# OSSI-1_EPS_2.net
KiCad netlist of a schematic drawn in Altium Designer
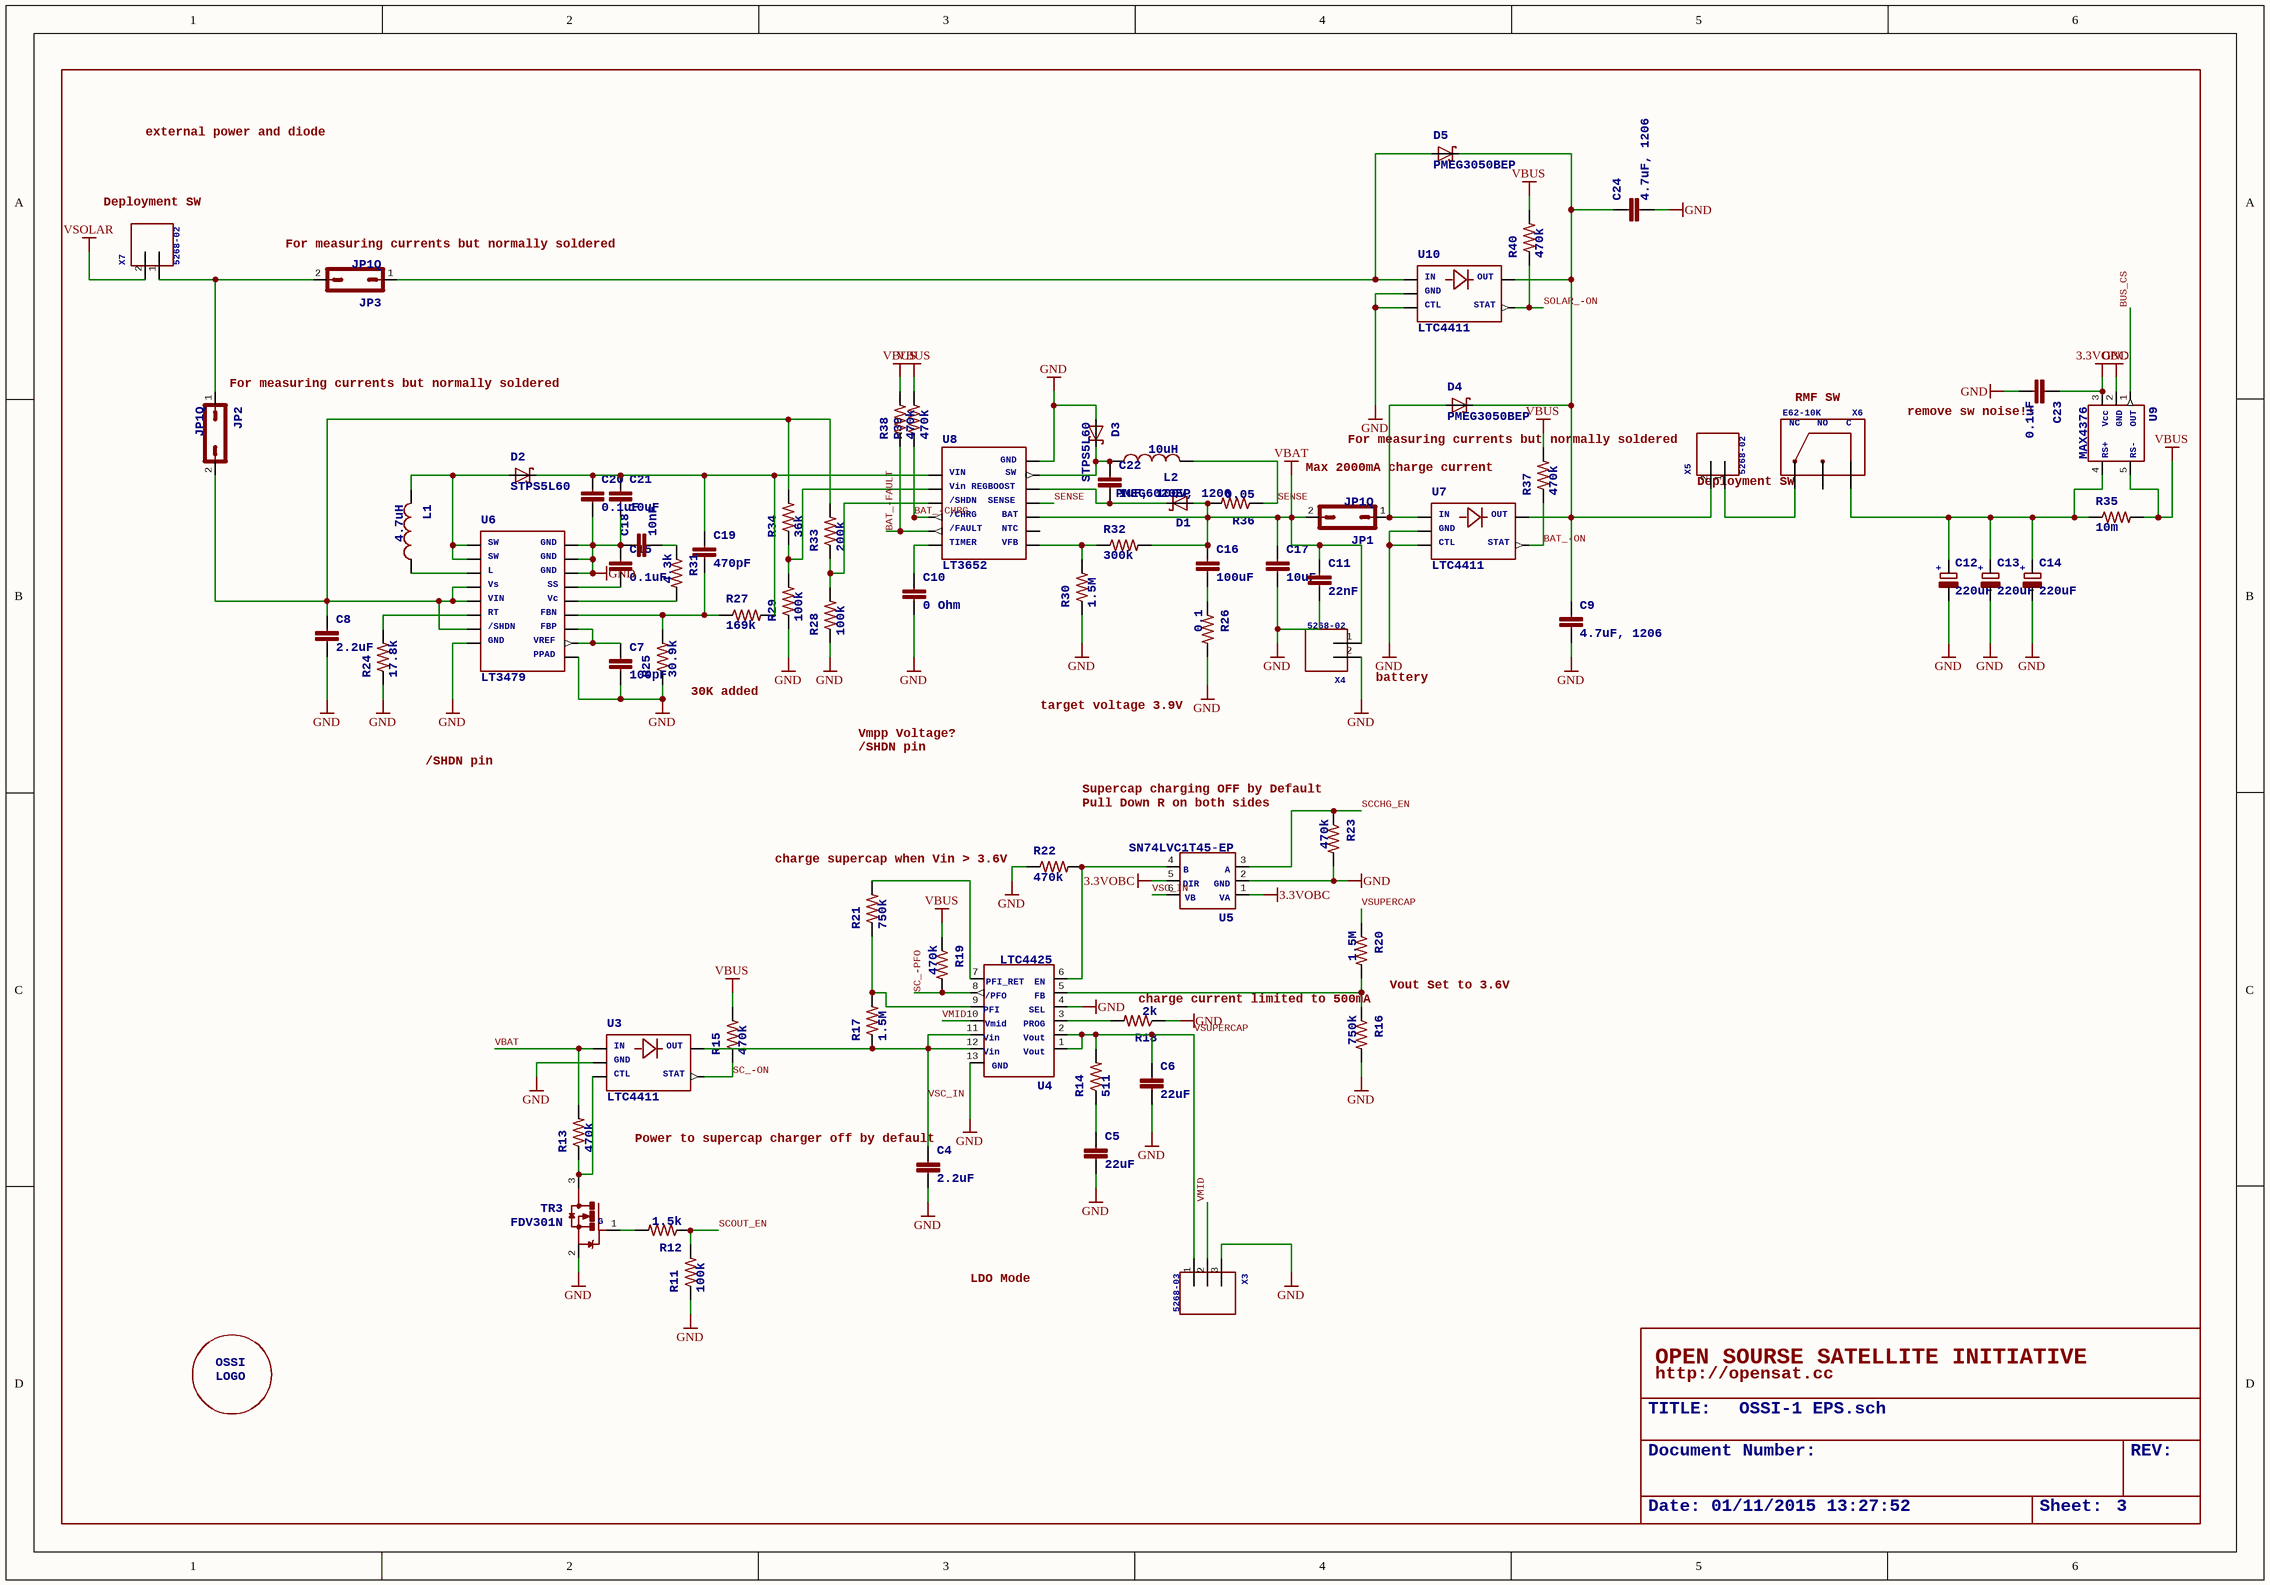
[diagram p0: OSSI-1 EPS_2.SchDoc]

(export (version "E")
  (design (tool "Eeschema 10.0.6"))
  (components
    (comp (ref "C4")
      (value "2.2uF")
      (footprint "C1206-GCM31")
      (fields (field (name ">NAME") "C4") (field (name ">VALUE") "2.2uF"))
      (libsource (lib "OSSI") (part "C1206(3216)-GCM31"))
    )
    (comp (ref "C5")
      (value "22uF")
      (footprint "C1210-GCM32")
      (fields (field (name ">NAME") "C5") (field (name ">VALUE") "22uF"))
      (libsource (lib "OSSI") (part "C1210(3225)-GCM32"))
    )
    (comp (ref "C6")
      (value "22uF")
      (footprint "C1210-GCM32")
      (fields (field (name ">NAME") "C6") (field (name ">VALUE") "22uF"))
      (libsource (lib "OSSI") (part "C1210(3225)-GCM32"))
    )
    (comp (ref "C7")
      (value "100pF")
      (footprint "C0603(1608)")
      (fields (field (name ">NAME") "C7") (field (name ">VALUE") "100pF"))
      (libsource (lib "OSSI") (part "C0603(1608)"))
    )
    (comp (ref "C8")
      (value "2.2uF")
      (footprint "C1206-GCM31")
      (fields (field (name ">NAME") "C8") (field (name ">VALUE") "2.2uF"))
      (libsource (lib "OSSI") (part "C1206(3216)-GCM31"))
    )
    (comp (ref "C9")
      (value "4.7uF, 1206")
      (footprint "C1206-GCM31")
      (fields (field (name ">NAME") "C9") (field (name ">VALUE") "4.7uF, 1206"))
      (libsource (lib "OSSI") (part "C1206(3216)-GCM31"))
    )
    (comp (ref "C10")
      (value "0 Ohm")
      (footprint "C0603(1608)")
      (fields (field (name ">NAME") "C10") (field (name ">VALUE") "0 Ohm"))
      (libsource (lib "OSSI") (part "C0603(1608)"))
    )
    (comp (ref "C11")
      (value "22nF")
      (footprint "C0603(1608)")
      (fields (field (name ">NAME") "C11") (field (name ">VALUE") "22nF"))
      (libsource (lib "OSSI") (part "C0603(1608)"))
    )
    (comp (ref "C12")
      (value "220uF")
      (footprint "C2917(7343)-Y")
      (fields (field (name ">NAME") "C12") (field (name "+") "+") (field (name ">VALUE") "220uF"))
      (libsource (lib "OSSI") (part "C-TANTAL-Y"))
    )
    (comp (ref "C13")
      (value "220uF")
      (footprint "C2917(7343)-Y")
      (fields (field (name ">NAME") "C13") (field (name "+") "+") (field (name ">VALUE") "220uF"))
      (libsource (lib "OSSI") (part "C-TANTAL-Y"))
    )
    (comp (ref "C14")
      (value "220uF")
      (footprint "C2917(7343)-Y")
      (fields (field (name ">NAME") "C14") (field (name "+") "+") (field (name ">VALUE") "220uF"))
      (libsource (lib "OSSI") (part "C-TANTAL-Y"))
    )
    (comp (ref "C15")
      (value "0.1uF")
      (footprint "C0603(1608)")
      (fields (field (name ">NAME") "C15") (field (name ">VALUE") "0.1uF"))
      (libsource (lib "OSSI") (part "C0603(1608)"))
    )
    (comp (ref "C16")
      (value "100uF")
      (footprint "C1210-TMK325")
      (fields (field (name ">NAME") "C16") (field (name ">VALUE") "100uF"))
      (libsource (lib "OSSI") (part "C1210(3225)-TMK325"))
    )
    (comp (ref "C17")
      (value "10uF")
      (footprint "C1210-GCM32")
      (fields (field (name ">NAME") "C17") (field (name ">VALUE") "10uF"))
      (libsource (lib "OSSI") (part "C1210(3225)-GCM32"))
    )
    (comp (ref "C18")
      (value "10nF")
      (footprint "C0603(1608)")
      (fields (field (name ">NAME") "C18") (field (name ">VALUE") "10nF"))
      (libsource (lib "") (part "C0603(1608)_2"))
    )
    (comp (ref "C19")
      (value "470pF")
      (footprint "C0603(1608)")
      (fields (field (name ">NAME") "C19") (field (name ">VALUE") "470pF"))
      (libsource (lib "OSSI") (part "C0603(1608)"))
    )
    (comp (ref "C20")
      (value "0.1uF")
      (footprint "C0603(1608)")
      (fields (field (name ">NAME") "C20") (field (name ">VALUE") "0.1uF"))
      (libsource (lib "OSSI") (part "C0603(1608)"))
    )
    (comp (ref "C21")
      (value "10uF")
      (footprint "C1210-GCM32")
      (fields (field (name ">NAME") "C21") (field (name ">VALUE") "10uF"))
      (libsource (lib "OSSI") (part "C1210(3225)-GCM32"))
    )
    (comp (ref "C22")
      (value "1uF, 100V, 1206")
      (footprint "C0805(2012)")
      (fields (field (name ">NAME") "C22") (field (name ">VALUE") "1uF, 100V, 1206"))
      (libsource (lib "OSSI") (part "C0805(2012)"))
    )
    (comp (ref "C23")
      (value "0.1uF")
      (footprint "C0603(1608)")
      (fields (field (name ">NAME") "C23") (field (name ">VALUE") "0.1uF"))
      (libsource (lib "") (part "C0603(1608)_1"))
    )
    (comp (ref "C24")
      (value "4.7uF, 1206")
      (footprint "C1206-GCM31")
      (fields (field (name ">NAME") "C24") (field (name ">VALUE") "4.7uF, 1206"))
      (libsource (lib "") (part "C1206(3216)-GCM31_1"))
    )
    (comp (ref "D1")
      (value "PMEG6020EP")
      (footprint "PMEG6020EP")
      (fields (field (name ">NAME") "D1") (field (name ">VALUE") "PMEG6020EP"))
      (libsource (lib "OSSI") (part "PMEG6020EP"))
    )
    (comp (ref "D2")
      (value "STPS5L60")
      (footprint "STPS5L60")
      (description "<b>STPS5L60</b>\nIf: 5A / Vrrm: 60V / Vf: 0.47V @ 5A")
      (fields (field (name ">NAME") "D2") (field (name ">VALUE") "STPS5L60"))
      (libsource (lib "OSSI") (part "STPS5L60"))
    )
    (comp (ref "D3")
      (value "STPS5L60")
      (footprint "STPS5L60")
      (description "<b>STPS5L60</b>\nIf: 5A / Vrrm: 60V / Vf: 0.47V @ 5A")
      (fields (field (name ">NAME") "D3") (field (name ">VALUE") "STPS5L60"))
      (libsource (lib "OSSI") (part "STPS5L60"))
    )
    (comp (ref "D4")
      (value "PMEG3050BEP")
      (footprint "PMEG6020EP")
      (fields (field (name ">NAME") "D4") (field (name ">VALUE") "PMEG3050BEP"))
      (libsource (lib "OSSI") (part "PMEG6020EP"))
    )
    (comp (ref "D5")
      (value "PMEG3050BEP")
      (footprint "PMEG6020EP")
      (fields (field (name ">NAME") "D5") (field (name ">VALUE") "PMEG3050BEP"))
      (libsource (lib "OSSI") (part "PMEG6020EP"))
    )
    (comp (ref "JP1")
      (value "JP1Q")
      (footprint "JP1")
      (description "<b>JUMPER</b>")
      (fields (field (name ">NAME") "JP1") (field (name ">VALUE") "JP1Q"))
      (libsource (lib "OSSI") (part "JP1Q"))
    )
    (comp (ref "JP2")
      (value "JP1Q")
      (footprint "JP1")
      (description "<b>JUMPER</b>")
      (fields (field (name ">NAME") "JP2") (field (name ">VALUE") "JP1Q"))
      (libsource (lib "OSSI") (part "JP1Q"))
    )
    (comp (ref "JP3")
      (value "JP1Q")
      (footprint "JP1")
      (description "<b>JUMPER</b>")
      (fields (field (name ">NAME") "JP3") (field (name ">VALUE") "JP1Q"))
      (libsource (lib "OSSI") (part "JP1Q"))
    )
    (comp (ref "L1")
      (value "4.7uH")
      (footprint "RLF7030")
      (fields (field (name ">NAME") "L1") (field (name ">VALUE") "4.7uH"))
      (libsource (lib "OSSI") (part "LRLF7030"))
    )
    (comp (ref "L2")
      (value "10uH")
      (footprint "RLF12545")
      (fields (field (name ">NAME") "L2") (field (name ">VALUE") "10uH"))
      (libsource (lib "OSSI") (part "LRLF12545"))
    )
    (comp (ref "R11")
      (value "100k")
      (footprint "R0603(1608)")
      (fields (field (name ">NAME") "R11") (field (name ">VALUE") "100k"))
      (libsource (lib "OSSI") (part "R0603(1608)"))
    )
    (comp (ref "R12")
      (value "1.5k")
      (footprint "R0603(1608)")
      (fields (field (name ">NAME") "R12") (field (name ">VALUE") "1.5k"))
      (libsource (lib "OSSI") (part "R0603(1608)"))
    )
    (comp (ref "R13")
      (value "470k")
      (footprint "R0603(1608)")
      (fields (field (name ">NAME") "R13") (field (name ">VALUE") "470k"))
      (libsource (lib "OSSI") (part "R0603(1608)"))
    )
    (comp (ref "R14")
      (value "511")
      (footprint "WSL1206")
      (fields (field (name ">NAME") "R14") (field (name ">VALUE") "511"))
      (libsource (lib "OSSI") (part "RWSL1206"))
    )
    (comp (ref "R15")
      (value "470k")
      (footprint "R0603(1608)")
      (fields (field (name ">NAME") "R15") (field (name ">VALUE") "470k"))
      (libsource (lib "OSSI") (part "R0603(1608)"))
    )
    (comp (ref "R16")
      (value "750k")
      (footprint "R0603(1608)")
      (fields (field (name ">NAME") "R16") (field (name ">VALUE") "750k"))
      (libsource (lib "OSSI") (part "R0603(1608)"))
    )
    (comp (ref "R17")
      (value "1.5M")
      (footprint "R0603(1608)")
      (fields (field (name ">NAME") "R17") (field (name ">VALUE") "1.5M"))
      (libsource (lib "OSSI") (part "R0603(1608)"))
    )
    (comp (ref "R18")
      (value "2k")
      (footprint "R0603(1608)")
      (fields (field (name ">NAME") "R18") (field (name ">VALUE") "2k"))
      (libsource (lib "OSSI") (part "R0603(1608)"))
    )
    (comp (ref "R19")
      (value "470k")
      (footprint "R0603(1608)")
      (fields (field (name ">NAME") "R19") (field (name ">VALUE") "470k"))
      (libsource (lib "OSSI") (part "R0603(1608)"))
    )
    (comp (ref "R20")
      (value "1.5M")
      (footprint "R0603(1608)")
      (fields (field (name ">NAME") "R20") (field (name ">VALUE") "1.5M"))
      (libsource (lib "OSSI") (part "R0603(1608)"))
    )
    (comp (ref "R21")
      (value "750k")
      (footprint "R0603(1608)")
      (fields (field (name ">NAME") "R21") (field (name ">VALUE") "750k"))
      (libsource (lib "OSSI") (part "R0603(1608)"))
    )
    (comp (ref "R22")
      (value "470k")
      (footprint "R0603(1608)")
      (fields (field (name ">NAME") "R22") (field (name ">VALUE") "470k"))
      (libsource (lib "OSSI") (part "R0603(1608)"))
    )
    (comp (ref "R23")
      (value "470k")
      (footprint "R0603(1608)")
      (fields (field (name ">NAME") "R23") (field (name ">VALUE") "470k"))
      (libsource (lib "OSSI") (part "R0603(1608)"))
    )
    (comp (ref "R24")
      (value "17.8k")
      (footprint "R0603(1608)")
      (fields (field (name ">NAME") "R24") (field (name ">VALUE") "17.8k"))
      (libsource (lib "OSSI") (part "R0603(1608)"))
    )
    (comp (ref "R25")
      (value "30.9k")
      (footprint "R0603(1608)")
      (fields (field (name ">NAME") "R25") (field (name ">VALUE") "30.9k"))
      (libsource (lib "OSSI") (part "R0603(1608)"))
    )
    (comp (ref "R26")
      (value "0.1")
      (footprint "WSL1206")
      (fields (field (name ">NAME") "R26") (field (name ">VALUE") "0.1"))
      (libsource (lib "OSSI") (part "RWSL1206"))
    )
    (comp (ref "R27")
      (value "169k")
      (footprint "R0603(1608)")
      (fields (field (name ">NAME") "R27") (field (name ">VALUE") "169k"))
      (libsource (lib "OSSI") (part "R0603(1608)"))
    )
    (comp (ref "R28")
      (value "100k")
      (footprint "R0603(1608)")
      (fields (field (name ">NAME") "R28") (field (name ">VALUE") "100k"))
      (libsource (lib "OSSI") (part "R0603(1608)"))
    )
    (comp (ref "R29")
      (value "100k")
      (footprint "R0603(1608)")
      (fields (field (name ">NAME") "R29") (field (name ">VALUE") "100k"))
      (libsource (lib "OSSI") (part "R0603(1608)"))
    )
    (comp (ref "R30")
      (value "1.5M")
      (footprint "R0603(1608)")
      (fields (field (name ">NAME") "R30") (field (name ">VALUE") "1.5M"))
      (libsource (lib "OSSI") (part "R0603(1608)"))
    )
    (comp (ref "R31")
      (value "4.3k")
      (footprint "R0603(1608)")
      (fields (field (name ">NAME") "R31") (field (name ">VALUE") "4.3k"))
      (libsource (lib "OSSI") (part "R0603(1608)"))
    )
    (comp (ref "R32")
      (value "300k")
      (footprint "R0603(1608)")
      (fields (field (name ">NAME") "R32") (field (name ">VALUE") "300k"))
      (libsource (lib "OSSI") (part "R0603(1608)"))
    )
    (comp (ref "R33")
      (value "200k")
      (footprint "R0603(1608)")
      (fields (field (name ">NAME") "R33") (field (name ">VALUE") "200k"))
      (libsource (lib "OSSI") (part "R0603(1608)"))
    )
    (comp (ref "R34")
      (value "36k")
      (footprint "R0603(1608)")
      (fields (field (name ">NAME") "R34") (field (name ">VALUE") "36k"))
      (libsource (lib "OSSI") (part "R0603(1608)"))
    )
    (comp (ref "R35")
      (value "10m")
      (footprint "WSL1206")
      (fields (field (name ">NAME") "R35") (field (name ">VALUE") "10m"))
      (libsource (lib "OSSI") (part "RWSL1206"))
    )
    (comp (ref "R36")
      (value "0.05")
      (footprint "WSL1206")
      (fields (field (name ">NAME") "R36") (field (name ">VALUE") "0.05"))
      (libsource (lib "OSSI") (part "RWSL1206"))
    )
    (comp (ref "R37")
      (value "470k")
      (footprint "R0603(1608)")
      (fields (field (name ">NAME") "R37") (field (name ">VALUE") "470k"))
      (libsource (lib "OSSI") (part "R0603(1608)"))
    )
    (comp (ref "R38")
      (value "470k")
      (footprint "R0603(1608)")
      (fields (field (name ">NAME") "R38") (field (name ">VALUE") "470k"))
      (libsource (lib "OSSI") (part "R0603(1608)"))
    )
    (comp (ref "R39")
      (value "470k")
      (footprint "R0603(1608)")
      (fields (field (name ">NAME") "R39") (field (name ">VALUE") "470k"))
      (libsource (lib "OSSI") (part "R0603(1608)"))
    )
    (comp (ref "R40")
      (value "470k")
      (footprint "R0603(1608)")
      (fields (field (name ">NAME") "R40") (field (name ">VALUE") "470k"))
      (libsource (lib "OSSI") (part "R0603(1608)"))
    )
    (comp (ref "TR3")
      (value "FDV301N")
      (footprint "SOT23")
      (description "FDV301N Digital N channel - FET / Rdson = 5 Ohm / Vgs = 0.7~1.06V / Ids = 220mA")
      (fields (field (name "G") "G") (field (name ">NAME") "TR3") (field (name ">VALUE") "FDV301N"))
      (libsource (lib "OSSI") (part "FDV301N"))
    )
    (comp (ref "U$1")
      (value "OSSILOGORECT")
      (footprint "OSSILOGORECT1005")
      (fields (field (name "OSSI") "OSSI") (field (name "LOGO") "LOGO"))
      (libsource (lib "OSSI") (part "OSSILOGORECT"))
    )
    (comp (ref "U3")
      (value "LTC4411")
      (footprint "TSOT23-5")
      (fields
        (field (name "IN") "IN")
        (field (name "GND") "GND")
        (field (name "CTL") "CTL")
        (field (name "OUT") "OUT")
        (field (name "STAT") "STAT")
        (field (name ">NAME") "U3")
        (field (name ">VALUE") "LTC4411")
      )
      (libsource (lib "OSSI") (part "LTC4411"))
    )
    (comp (ref "U4")
      (value "LTC4425")
      (footprint "MSE")
      (description "LTC4425 Linear SuperCap Charger With Current-Limited Ideal Diode and V/I Monitor")
      (fields
        (field (name ">NAME") "U4")
        (field (name ">VALUE") "LTC4425")
        (field (name "VOUT") "Vout")
        (field (name "VOUT_1") "Vout")
        (field (name "PROG") "PROG")
        (field (name "SEL") "SEL")
        (field (name "FB") "FB")
        (field (name "EN") "EN")
        (field (name "PFI_RET") "PFI_RET")
        (field (name "/PFO") "/PFO")
        (field (name "VMID") "Vmid")
        (field (name "VIN") "Vin")
        (field (name "VIN_1") "Vin")
        (field (name "PFI") "PFI")
        (field (name "GND") "GND")
      )
      (libsource (lib "OSSI") (part "LTC4425"))
    )
    (comp (ref "U5")
      (value "SN74LVC1T45-EP")
      (footprint "SOT-6DCK")
      (fields
        (field (name ">NAME") "U5")
        (field (name ">VALUE") "SN74LVC1T45-EP")
        (field (name "VA") "VA")
        (field (name "GND") "GND")
        (field (name "A") "A")
        (field (name "B") "B")
        (field (name "DIR") "DIR")
        (field (name "VB") "VB")
      )
      (libsource (lib "OSSI") (part "SN74LVC1T45-EP"))
    )
    (comp (ref "U6")
      (value "LT3479")
      (footprint "TSSOP16-FE")
      (fields
        (field (name "SW") "SW")
        (field (name "SW_1") "SW")
        (field (name "L") "L")
        (field (name "VS") "Vs")
        (field (name "VIN") "VIN")
        (field (name "RT") "RT")
        (field (name "/SHDN") "/SHDN")
        (field (name "GND") "GND")
        (field (name "GND_1") "GND")
        (field (name "GND_2") "GND")
        (field (name "GND_3") "GND")
        (field (name "SS") "SS")
        (field (name "VC") "Vc")
        (field (name "FBN") "FBN")
        (field (name "FBP") "FBP")
        (field (name "VREF") "VREF")
        (field (name ">NAME") "U6")
        (field (name ">VALUE") "LT3479")
        (field (name "PPAD") "PPAD")
      )
      (libsource (lib "OSSI") (part "LT3479"))
    )
    (comp (ref "U7")
      (value "LTC4411")
      (footprint "TSOT23-5")
      (fields
        (field (name "IN") "IN")
        (field (name "GND") "GND")
        (field (name "CTL") "CTL")
        (field (name "OUT") "OUT")
        (field (name "STAT") "STAT")
        (field (name ">NAME") "U7")
        (field (name ">VALUE") "LTC4411")
      )
      (libsource (lib "OSSI") (part "LTC4411"))
    )
    (comp (ref "U8")
      (value "LT3652")
      (footprint "MSE")
      (fields
        (field (name "VIN") "VIN")
        (field (name "VIN REG") "Vin REG")
        (field (name "/SHDN") "/SHDN")
        (field (name "/CHRG") "/CHRG")
        (field (name "/FAULT") "/FAULT")
        (field (name "TIMER") "TIMER")
        (field (name "VFB") "VFB")
        (field (name "NTC") "NTC")
        (field (name "BAT") "BAT")
        (field (name "SENSE") "SENSE")
        (field (name "BOOST") "BOOST")
        (field (name "SW") "SW")
        (field (name ">NAME") "U8")
        (field (name ">VALUE") "LT3652")
        (field (name "GND") "GND")
      )
      (libsource (lib "OSSI") (part "LT3652"))
    )
    (comp (ref "U9")
      (value "MAX4376")
      (footprint "SOT23-5DBV")
      (fields
        (field (name ">NAME") "U9")
        (field (name ">VALUE") "MAX4376")
        (field (name "OUT") "OUT")
        (field (name "GND") "GND")
        (field (name "VCC") "Vcc")
        (field (name "RS+") "RS+")
        (field (name "RS-") "RS-")
      )
      (libsource (lib "OSSI") (part "MAX4376"))
    )
    (comp (ref "U10")
      (value "LTC4411")
      (footprint "TSOT23-5")
      (fields
        (field (name "IN") "IN")
        (field (name "GND") "GND")
        (field (name "CTL") "CTL")
        (field (name "OUT") "OUT")
        (field (name "STAT") "STAT")
        (field (name ">NAME") "U10")
        (field (name ">VALUE") "LTC4411")
      )
      (libsource (lib "OSSI") (part "LTC4411"))
    )
    (comp (ref "X3")
      (value "5268-03")
      (footprint "5268-03")
      (fields (field (name ">NAME") "X3") (field (name ">VALUE") "5268-03"))
      (libsource (lib "OSSI") (part "5268-03"))
    )
    (comp (ref "X4")
      (value "5268-02")
      (footprint "5628-02")
      (fields (field (name ">NAME") "X4") (field (name ">VALUE") "5268-02"))
      (libsource (lib "OSSI") (part "5268-02"))
    )
    (comp (ref "X5")
      (value "5268-02")
      (footprint "5628-02")
      (fields (field (name ">NAME") "X5") (field (name ">VALUE") "5268-02"))
      (libsource (lib "OSSI") (part "5268-02"))
    )
    (comp (ref "X6")
      (value "E62-10K")
      (footprint "E62-10K")
      (description "Cherry E620-10K spdt sw for Remove Before Flight pin")
      (fields
        (field (name ">NAME") "X6")
        (field (name ">VALUE") "E62-10K")
        (field (name "C") "C")
        (field (name "NO") "NO")
        (field (name "NC") "NC")
      )
      (libsource (lib "OSSI") (part "E62-10K"))
    )
    (comp (ref "X7")
      (value "5268-02")
      (footprint "5628-02")
      (fields (field (name ">NAME") "X7") (field (name ">VALUE") "5268-02"))
      (libsource (lib "OSSI") (part "5268-02"))
    )
  )
  (nets
    (net (code "1") (name "/BAT_-CHRG") (class "Default")
      (node (ref "R39") (pin "1") (pinfunction "1_1") (pintype "passive"))
      (node (ref "U8") (pin "4") (pinfunction "P$4_4") (pintype "output"))
    )
    (net (code "2") (name "/BAT_-FAULT") (class "Default")
      (node (ref "R38") (pin "1") (pinfunction "1_1") (pintype "passive"))
      (node (ref "U8") (pin "5") (pinfunction "P$5_5") (pintype "output"))
    )
    (net (code "3") (name "/BAT_-ON") (class "Default")
      (node (ref "R37") (pin "1") (pinfunction "1_1") (pintype "passive"))
      (node (ref "U7") (pin "P$4") (pinfunction "P$4_P$4") (pintype "output"))
    )
    (net (code "4") (name "/BUS_CS") (class "Default")
      (node (ref "U9") (pin "1") (pinfunction "P$1_1") (pintype "output"))
    )
    (net (code "5") (name "/SCCHG_EN") (class "Default")
      (node (ref "R23") (pin "1") (pinfunction "1_1") (pintype "passive"))
      (node (ref "U5") (pin "3") (pinfunction "P$3_3") (pintype "passive"))
    )
    (net (code "6") (name "/SCOUT_EN") (class "Default")
      (node (ref "R11") (pin "2") (pinfunction "2_2") (pintype "passive"))
      (node (ref "R12") (pin "1") (pinfunction "1_1") (pintype "passive"))
    )
    (net (code "7") (name "/SC_-ON") (class "Default")
      (node (ref "R15") (pin "1") (pinfunction "1_1") (pintype "passive"))
      (node (ref "U3") (pin "P$4") (pinfunction "P$4_P$4") (pintype "output"))
    )
    (net (code "8") (name "/SC_-PFO") (class "Default")
      (node (ref "R19") (pin "2") (pinfunction "2_2") (pintype "passive"))
      (node (ref "U4") (pin "8") (pinfunction "P$8_8") (pintype "output"))
    )
    (net (code "9") (name "/SENSE") (class "Default")
      (node (ref "L2") (pin "P$2") (pinfunction "2_P$2") (pintype "passive"))
      (node (ref "R36") (pin "P$1") (pinfunction "1_P$1") (pintype "passive"))
      (node (ref "U8") (pin "10") (pinfunction "P$10_10") (pintype "passive"))
    )
    (net (code "10") (name "/SOLAR_-ON") (class "Default")
      (node (ref "R40") (pin "1") (pinfunction "1_1") (pintype "passive"))
      (node (ref "U10") (pin "P$4") (pinfunction "P$4_P$4") (pintype "output"))
    )
    (net (code "11") (name "/VMID") (class "Default")
      (node (ref "U4") (pin "10") (pinfunction "P$10_10") (pintype "power_in"))
      (node (ref "X3") (pin "2") (pinfunction "2_2") (pintype "passive"))
    )
    (net (code "12") (name "/VSC_IN") (class "Default")
      (node (ref "C4") (pin "P$1") (pinfunction "1_P$1") (pintype "passive"))
      (node (ref "R17") (pin "1") (pinfunction "1_1") (pintype "passive"))
      (node (ref "U3") (pin "P$5") (pinfunction "P$5_P$5") (pintype "power_in"))
      (node (ref "U4") (pin "11") (pinfunction "P$11_11") (pintype "power_in"))
      (node (ref "U4") (pin "12") (pinfunction "P$12_12") (pintype "power_in"))
      (node (ref "U5") (pin "6") (pinfunction "P$6_6") (pintype "passive"))
    )
    (net (code "13") (name "/VSUPERCAP") (class "Default")
      (node (ref "C6") (pin "P$1") (pinfunction "1_P$1") (pintype "passive"))
      (node (ref "R14") (pin "P$2") (pinfunction "2_P$2") (pintype "passive"))
      (node (ref "R20") (pin "1") (pinfunction "1_1") (pintype "passive"))
      (node (ref "U4") (pin "1") (pinfunction "P$1_1") (pintype "power_in"))
      (node (ref "U4") (pin "2") (pinfunction "P$2_2") (pintype "power_in"))
      (node (ref "X3") (pin "1") (pinfunction "1_1") (pintype "passive"))
    )
    (net (code "14") (name "3.3VOBC") (class "Default")
      (node (ref "C23") (pin "1") (pinfunction "1_1") (pintype "passive"))
      (node (ref "U5") (pin "1") (pinfunction "P$1_1") (pintype "passive"))
      (node (ref "U5") (pin "5") (pinfunction "P$5_5") (pintype "passive"))
      (node (ref "U9") (pin "3") (pinfunction "P$3_3") (pintype "power_in"))
    )
    (net (code "15") (name "GND") (class "Default")
      (node (ref "C10") (pin "2") (pinfunction "2_2") (pintype "passive"))
      (node (ref "C11") (pin "2") (pinfunction "2_2") (pintype "passive"))
      (node (ref "C12") (pin "2") (pinfunction "-_2") (pintype "passive"))
      (node (ref "C13") (pin "2") (pinfunction "-_2") (pintype "passive"))
      (node (ref "C14") (pin "2") (pinfunction "-_2") (pintype "passive"))
      (node (ref "C15") (pin "1") (pinfunction "1_1") (pintype "passive"))
      (node (ref "C17") (pin "P$2") (pinfunction "2_P$2") (pintype "passive"))
      (node (ref "C18") (pin "1") (pinfunction "1_1") (pintype "passive"))
      (node (ref "C20") (pin "2") (pinfunction "2_2") (pintype "passive"))
      (node (ref "C21") (pin "P$2") (pinfunction "2_P$2") (pintype "passive"))
      (node (ref "C23") (pin "2") (pinfunction "2_2") (pintype "passive"))
      (node (ref "C24") (pin "P$2") (pinfunction "2_P$2") (pintype "passive"))
      (node (ref "C4") (pin "P$2") (pinfunction "2_P$2") (pintype "passive"))
      (node (ref "C5") (pin "P$2") (pinfunction "2_P$2") (pintype "passive"))
      (node (ref "C6") (pin "P$2") (pinfunction "2_P$2") (pintype "passive"))
      (node (ref "C7") (pin "2") (pinfunction "2_2") (pintype "passive"))
      (node (ref "C8") (pin "P$2") (pinfunction "2_P$2") (pintype "passive"))
      (node (ref "C9") (pin "P$2") (pinfunction "2_P$2") (pintype "passive"))
      (node (ref "D3") (pin "A") (pinfunction "A_A") (pintype "passive"))
      (node (ref "R11") (pin "1") (pinfunction "1_1") (pintype "passive"))
      (node (ref "R16") (pin "2") (pinfunction "2_2") (pintype "passive"))
      (node (ref "R18") (pin "1") (pinfunction "1_1") (pintype "passive"))
      (node (ref "R22") (pin "1") (pinfunction "1_1") (pintype "passive"))
      (node (ref "R23") (pin "2") (pinfunction "2_2") (pintype "passive"))
      (node (ref "R24") (pin "1") (pinfunction "1_1") (pintype "passive"))
      (node (ref "R25") (pin "1") (pinfunction "1_1") (pintype "passive"))
      (node (ref "R26") (pin "P$2") (pinfunction "2_P$2") (pintype "passive"))
      (node (ref "R28") (pin "1") (pinfunction "1_1") (pintype "passive"))
      (node (ref "R29") (pin "1") (pinfunction "1_1") (pintype "passive"))
      (node (ref "R30") (pin "1") (pinfunction "1_1") (pintype "passive"))
      (node (ref "TR3") (pin "2") (pinfunction "S_2") (pintype "passive"))
      (node (ref "U10") (pin "P$2") (pinfunction "P$2_P$2") (pintype "power_in"))
      (node (ref "U10") (pin "P$3") (pinfunction "P$3_P$3") (pintype "passive"))
      (node (ref "U3") (pin "P$2") (pinfunction "P$2_P$2") (pintype "power_in"))
      (node (ref "U4") (pin "13") (pinfunction "P$13_13") (pintype "power_in"))
      (node (ref "U4") (pin "4") (pinfunction "P$4_4") (pintype "passive"))
      (node (ref "U5") (pin "2") (pinfunction "P$2_2") (pintype "passive"))
      (node (ref "U6") (pin "14") (pinfunction "P$14_14") (pintype "power_in"))
      (node (ref "U6") (pin "15") (pinfunction "P$15_15") (pintype "power_in"))
      (node (ref "U6") (pin "16") (pinfunction "P$16_16") (pintype "power_in"))
      (node (ref "U6") (pin "8") (pinfunction "P$8_8") (pintype "power_in"))
      (node (ref "U6") (pin "PPAD") (pinfunction "P$17_PPAD") (pintype "power_in"))
      (node (ref "U7") (pin "P$2") (pinfunction "P$2_P$2") (pintype "power_in"))
      (node (ref "U7") (pin "P$3") (pinfunction "P$3_P$3") (pintype "passive"))
      (node (ref "U8") (pin "13") (pinfunction "P$13_13") (pintype "passive"))
      (node (ref "U9") (pin "2") (pinfunction "P$2_2") (pintype "power_in"))
      (node (ref "X3") (pin "3") (pinfunction "3_3") (pintype "passive"))
      (node (ref "X4") (pin "2") (pinfunction "2_2") (pintype "passive"))
    )
    (net (code "16") (name "Net-(C5-1)") (class "Default")
      (node (ref "C5") (pin "P$1") (pinfunction "1_P$1") (pintype "passive"))
      (node (ref "R14") (pin "P$1") (pinfunction "1_P$1") (pintype "passive"))
    )
    (net (code "17") (name "Net-(C8-1)") (class "Default")
      (node (ref "C8") (pin "P$1") (pinfunction "1_P$1") (pintype "passive"))
      (node (ref "JP2") (pin "2") (pinfunction "2_2") (pintype "passive"))
      (node (ref "R33") (pin "2") (pinfunction "2_2") (pintype "passive"))
      (node (ref "R34") (pin "2") (pinfunction "2_2") (pintype "passive"))
      (node (ref "U6") (pin "4") (pinfunction "P$4_4") (pintype "power_in"))
      (node (ref "U6") (pin "5") (pinfunction "P$5_5") (pintype "power_in"))
      (node (ref "U6") (pin "7") (pinfunction "P$7_7") (pintype "passive"))
    )
    (net (code "18") (name "Net-(C12-+)") (class "Default")
      (node (ref "C12") (pin "1") (pinfunction "+_1") (pintype "passive"))
      (node (ref "C13") (pin "1") (pinfunction "+_1") (pintype "passive"))
      (node (ref "C14") (pin "1") (pinfunction "+_1") (pintype "passive"))
      (node (ref "R35") (pin "P$1") (pinfunction "1_P$1") (pintype "passive"))
      (node (ref "U9") (pin "4") (pinfunction "P$4_4") (pintype "passive"))
      (node (ref "X6") (pin "C") (pinfunction "C_C") (pintype "passive"))
    )
    (net (code "19") (name "Net-(C16-2)") (class "Default")
      (node (ref "C16") (pin "P$2") (pinfunction "2_P$2") (pintype "passive"))
      (node (ref "R26") (pin "P$1") (pinfunction "1_P$1") (pintype "passive"))
    )
    (net (code "20") (name "Net-(C18-Pad2)") (class "Default")
      (node (ref "C18") (pin "2") (pinfunction "2_2") (pintype "passive"))
      (node (ref "R31") (pin "1") (pinfunction "1_1") (pintype "passive"))
    )
    (net (code "21") (name "Net-(C21-1)") (class "Default")
      (node (ref "C19") (pin "1") (pinfunction "1_1") (pintype "passive"))
      (node (ref "C20") (pin "1") (pinfunction "1_1") (pintype "passive"))
      (node (ref "C21") (pin "P$1") (pinfunction "1_P$1") (pintype "passive"))
      (node (ref "D2") (pin "C") (pinfunction "C_C") (pintype "passive"))
      (node (ref "R27") (pin "2") (pinfunction "2_2") (pintype "passive"))
      (node (ref "U8") (pin "1") (pinfunction "P$1_1") (pintype "power_in"))
    )
    (net (code "22") (name "Net-(C24-1)") (class "Default")
      (node (ref "C24") (pin "P$1") (pinfunction "1_P$1") (pintype "passive"))
      (node (ref "C9") (pin "P$1") (pinfunction "1_P$1") (pintype "passive"))
      (node (ref "D4") (pin "C") (pinfunction "C_C") (pintype "passive"))
      (node (ref "D5") (pin "C") (pinfunction "C_C") (pintype "passive"))
      (node (ref "U10") (pin "P$5") (pinfunction "P$5_P$5") (pintype "power_in"))
      (node (ref "U7") (pin "P$5") (pinfunction "P$5_P$5") (pintype "power_in"))
      (node (ref "X5") (pin "2") (pinfunction "2_2") (pintype "passive"))
    )
    (net (code "23") (name "Net-(D4-PadA)") (class "Default")
      (node (ref "D4") (pin "A") (pinfunction "A_A") (pintype "passive"))
      (node (ref "JP1") (pin "1") (pinfunction "1_1") (pintype "passive"))
      (node (ref "U7") (pin "P$1") (pinfunction "P$1_P$1") (pintype "passive"))
    )
    (net (code "24") (name "Net-(D5-PadA)") (class "Default")
      (node (ref "D5") (pin "A") (pinfunction "A_A") (pintype "passive"))
      (node (ref "JP3") (pin "1") (pinfunction "1_1") (pintype "passive"))
      (node (ref "U10") (pin "P$1") (pinfunction "P$1_P$1") (pintype "passive"))
    )
    (net (code "25") (name "Net-(JP2-Pad1)") (class "Default")
      (node (ref "JP2") (pin "1") (pinfunction "1_1") (pintype "passive"))
      (node (ref "JP3") (pin "2") (pinfunction "2_2") (pintype "passive"))
      (node (ref "X7") (pin "1") (pinfunction "1_1") (pintype "passive"))
    )
    (net (code "26") (name "Net-(L1-1)") (class "Default")
      (node (ref "L1") (pin "P$1") (pinfunction "1_P$1") (pintype "passive"))
      (node (ref "U6") (pin "3") (pinfunction "P$3_3") (pintype "passive"))
    )
    (net (code "27") (name "Net-(L1-2)") (class "Default")
      (node (ref "D2") (pin "A") (pinfunction "A_A") (pintype "passive"))
      (node (ref "L1") (pin "P$2") (pinfunction "2_P$2") (pintype "passive"))
      (node (ref "U6") (pin "1") (pinfunction "P$1_1") (pintype "power_in"))
      (node (ref "U6") (pin "2") (pinfunction "P$2_2") (pintype "power_in"))
    )
    (net (code "28") (name "Net-(L2-1)") (class "Default")
      (node (ref "C22") (pin "1") (pinfunction "1_1") (pintype "passive"))
      (node (ref "D3") (pin "C") (pinfunction "C_C") (pintype "passive"))
      (node (ref "L2") (pin "P$1") (pinfunction "1_P$1") (pintype "passive"))
      (node (ref "U8") (pin "12") (pinfunction "P$12_12") (pintype "output"))
    )
    (net (code "29") (name "Net-(TR3-D)") (class "Default")
      (node (ref "R13") (pin "1") (pinfunction "1_1") (pintype "passive"))
      (node (ref "TR3") (pin "3") (pinfunction "D_3") (pintype "passive"))
      (node (ref "U3") (pin "P$3") (pinfunction "P$3_P$3") (pintype "passive"))
    )
    (net (code "30") (name "Net-(TR3-G)") (class "Default")
      (node (ref "R12") (pin "2") (pinfunction "2_2") (pintype "passive"))
      (node (ref "TR3") (pin "1") (pinfunction "G_1") (pintype "passive"))
    )
    (net (code "31") (name "Net-(U4-P$3)") (class "Default")
      (node (ref "R18") (pin "2") (pinfunction "2_2") (pintype "passive"))
      (node (ref "U4") (pin "3") (pinfunction "P$3_3") (pintype "passive"))
    )
    (net (code "32") (name "Net-(U4-P$5)") (class "Default")
      (node (ref "R16") (pin "1") (pinfunction "1_1") (pintype "passive"))
      (node (ref "R20") (pin "2") (pinfunction "2_2") (pintype "passive"))
      (node (ref "U4") (pin "5") (pinfunction "P$5_5") (pintype "passive"))
    )
    (net (code "33") (name "Net-(U4-P$6)") (class "Default")
      (node (ref "R22") (pin "2") (pinfunction "2_2") (pintype "passive"))
      (node (ref "U4") (pin "6") (pinfunction "P$6_6") (pintype "passive"))
      (node (ref "U5") (pin "4") (pinfunction "P$4_4") (pintype "passive"))
    )
    (net (code "34") (name "Net-(U4-P$7)") (class "Default")
      (node (ref "R21") (pin "2") (pinfunction "2_2") (pintype "passive"))
      (node (ref "U4") (pin "7") (pinfunction "P$7_7") (pintype "passive"))
    )
    (net (code "35") (name "Net-(U4-P$9)") (class "Default")
      (node (ref "R17") (pin "2") (pinfunction "2_2") (pintype "passive"))
      (node (ref "R21") (pin "1") (pinfunction "1_1") (pintype "passive"))
      (node (ref "U4") (pin "9") (pinfunction "P$9_9") (pintype "passive"))
    )
    (net (code "36") (name "Net-(U6-P$6)") (class "Default")
      (node (ref "R24") (pin "2") (pinfunction "2_2") (pintype "passive"))
      (node (ref "U6") (pin "6") (pinfunction "P$6_6") (pintype "passive"))
    )
    (net (code "37") (name "Net-(U6-P$10)") (class "Default")
      (node (ref "C7") (pin "1") (pinfunction "1_1") (pintype "passive"))
      (node (ref "U6") (pin "10") (pinfunction "P$10_10") (pintype "passive"))
      (node (ref "U6") (pin "9") (pinfunction "P$9_9") (pintype "output"))
    )
    (net (code "38") (name "Net-(U6-P$11)") (class "Default")
      (node (ref "C19") (pin "2") (pinfunction "2_2") (pintype "passive"))
      (node (ref "R25") (pin "2") (pinfunction "2_2") (pintype "passive"))
      (node (ref "R27") (pin "1") (pinfunction "1_1") (pintype "passive"))
      (node (ref "U6") (pin "11") (pinfunction "P$11_11") (pintype "passive"))
    )
    (net (code "39") (name "Net-(U6-P$12)") (class "Default")
      (node (ref "R31") (pin "2") (pinfunction "2_2") (pintype "passive"))
      (node (ref "U6") (pin "12") (pinfunction "P$12_12") (pintype "passive"))
    )
    (net (code "40") (name "Net-(U6-P$13)") (class "Default")
      (node (ref "C15") (pin "2") (pinfunction "2_2") (pintype "passive"))
      (node (ref "U6") (pin "13") (pinfunction "P$13_13") (pintype "passive"))
    )
    (net (code "41") (name "Net-(U8-P$2)") (class "Default")
      (node (ref "R29") (pin "2") (pinfunction "2_2") (pintype "passive"))
      (node (ref "R34") (pin "1") (pinfunction "1_1") (pintype "passive"))
      (node (ref "U8") (pin "2") (pinfunction "P$2_2") (pintype "passive"))
    )
    (net (code "42") (name "Net-(U8-P$3)") (class "Default")
      (node (ref "R28") (pin "2") (pinfunction "2_2") (pintype "passive"))
      (node (ref "R33") (pin "1") (pinfunction "1_1") (pintype "passive"))
      (node (ref "U8") (pin "3") (pinfunction "P$3_3") (pintype "passive"))
    )
    (net (code "43") (name "Net-(U8-P$6)") (class "Default")
      (node (ref "C10") (pin "1") (pinfunction "1_1") (pintype "passive"))
      (node (ref "U8") (pin "6") (pinfunction "P$6_6") (pintype "passive"))
    )
    (net (code "44") (name "Net-(U8-P$7)") (class "Default")
      (node (ref "R30") (pin "2") (pinfunction "2_2") (pintype "passive"))
      (node (ref "R32") (pin "1") (pinfunction "1_1") (pintype "passive"))
      (node (ref "U8") (pin "7") (pinfunction "P$7_7") (pintype "passive"))
    )
    (net (code "45") (name "Net-(U8-P$11)") (class "Default")
      (node (ref "C22") (pin "2") (pinfunction "2_2") (pintype "passive"))
      (node (ref "D1") (pin "C") (pinfunction "C_C") (pintype "passive"))
      (node (ref "U8") (pin "11") (pinfunction "P$11_11") (pintype "passive"))
    )
    (net (code "46") (name "Net-(X5-Pad1)") (class "Default")
      (node (ref "X5") (pin "1") (pinfunction "1_1") (pintype "passive"))
      (node (ref "X6") (pin "NC") (pinfunction "NC_NC") (pintype "passive"))
    )
    (net (code "47") (name "VBAT") (class "Default")
      (node (ref "C11") (pin "1") (pinfunction "1_1") (pintype "passive"))
      (node (ref "C16") (pin "P$1") (pinfunction "1_P$1") (pintype "passive"))
      (node (ref "C17") (pin "P$1") (pinfunction "1_P$1") (pintype "passive"))
      (node (ref "D1") (pin "A") (pinfunction "A_A") (pintype "passive"))
      (node (ref "JP1") (pin "2") (pinfunction "2_2") (pintype "passive"))
      (node (ref "R13") (pin "2") (pinfunction "2_2") (pintype "passive"))
      (node (ref "R32") (pin "2") (pinfunction "2_2") (pintype "passive"))
      (node (ref "R36") (pin "P$2") (pinfunction "2_P$2") (pintype "passive"))
      (node (ref "U3") (pin "P$1") (pinfunction "P$1_P$1") (pintype "passive"))
      (node (ref "U8") (pin "9") (pinfunction "P$9_9") (pintype "passive"))
      (node (ref "X4") (pin "1") (pinfunction "1_1") (pintype "passive"))
    )
    (net (code "48") (name "VBUS") (class "Default")
      (node (ref "R15") (pin "2") (pinfunction "2_2") (pintype "passive"))
      (node (ref "R19") (pin "1") (pinfunction "1_1") (pintype "passive"))
      (node (ref "R35") (pin "P$2") (pinfunction "2_P$2") (pintype "passive"))
      (node (ref "R37") (pin "2") (pinfunction "2_2") (pintype "passive"))
      (node (ref "R38") (pin "2") (pinfunction "2_2") (pintype "passive"))
      (node (ref "R39") (pin "2") (pinfunction "2_2") (pintype "passive"))
      (node (ref "R40") (pin "2") (pinfunction "2_2") (pintype "passive"))
      (node (ref "U9") (pin "5") (pinfunction "P$5_5") (pintype "passive"))
    )
    (net (code "49") (name "VSOLAR") (class "Default")
      (node (ref "X7") (pin "2") (pinfunction "2_2") (pintype "passive"))
    )
    (net (code "50") (name "unconnected-(U8-P$8-Pad8)") (class "Default")
      (node (ref "U8") (pin "8") (pinfunction "P$8_8") (pintype "passive"))
    )
    (net (code "51") (name "unconnected-(X6-PadNO)") (class "Default")
      (node (ref "X6") (pin "NO") (pinfunction "NO_NO") (pintype "passive"))
    )
  )
)
